# 9_RK3588_USB_Controler.net
KiCad netlist of a schematic drawn in Altium Designer
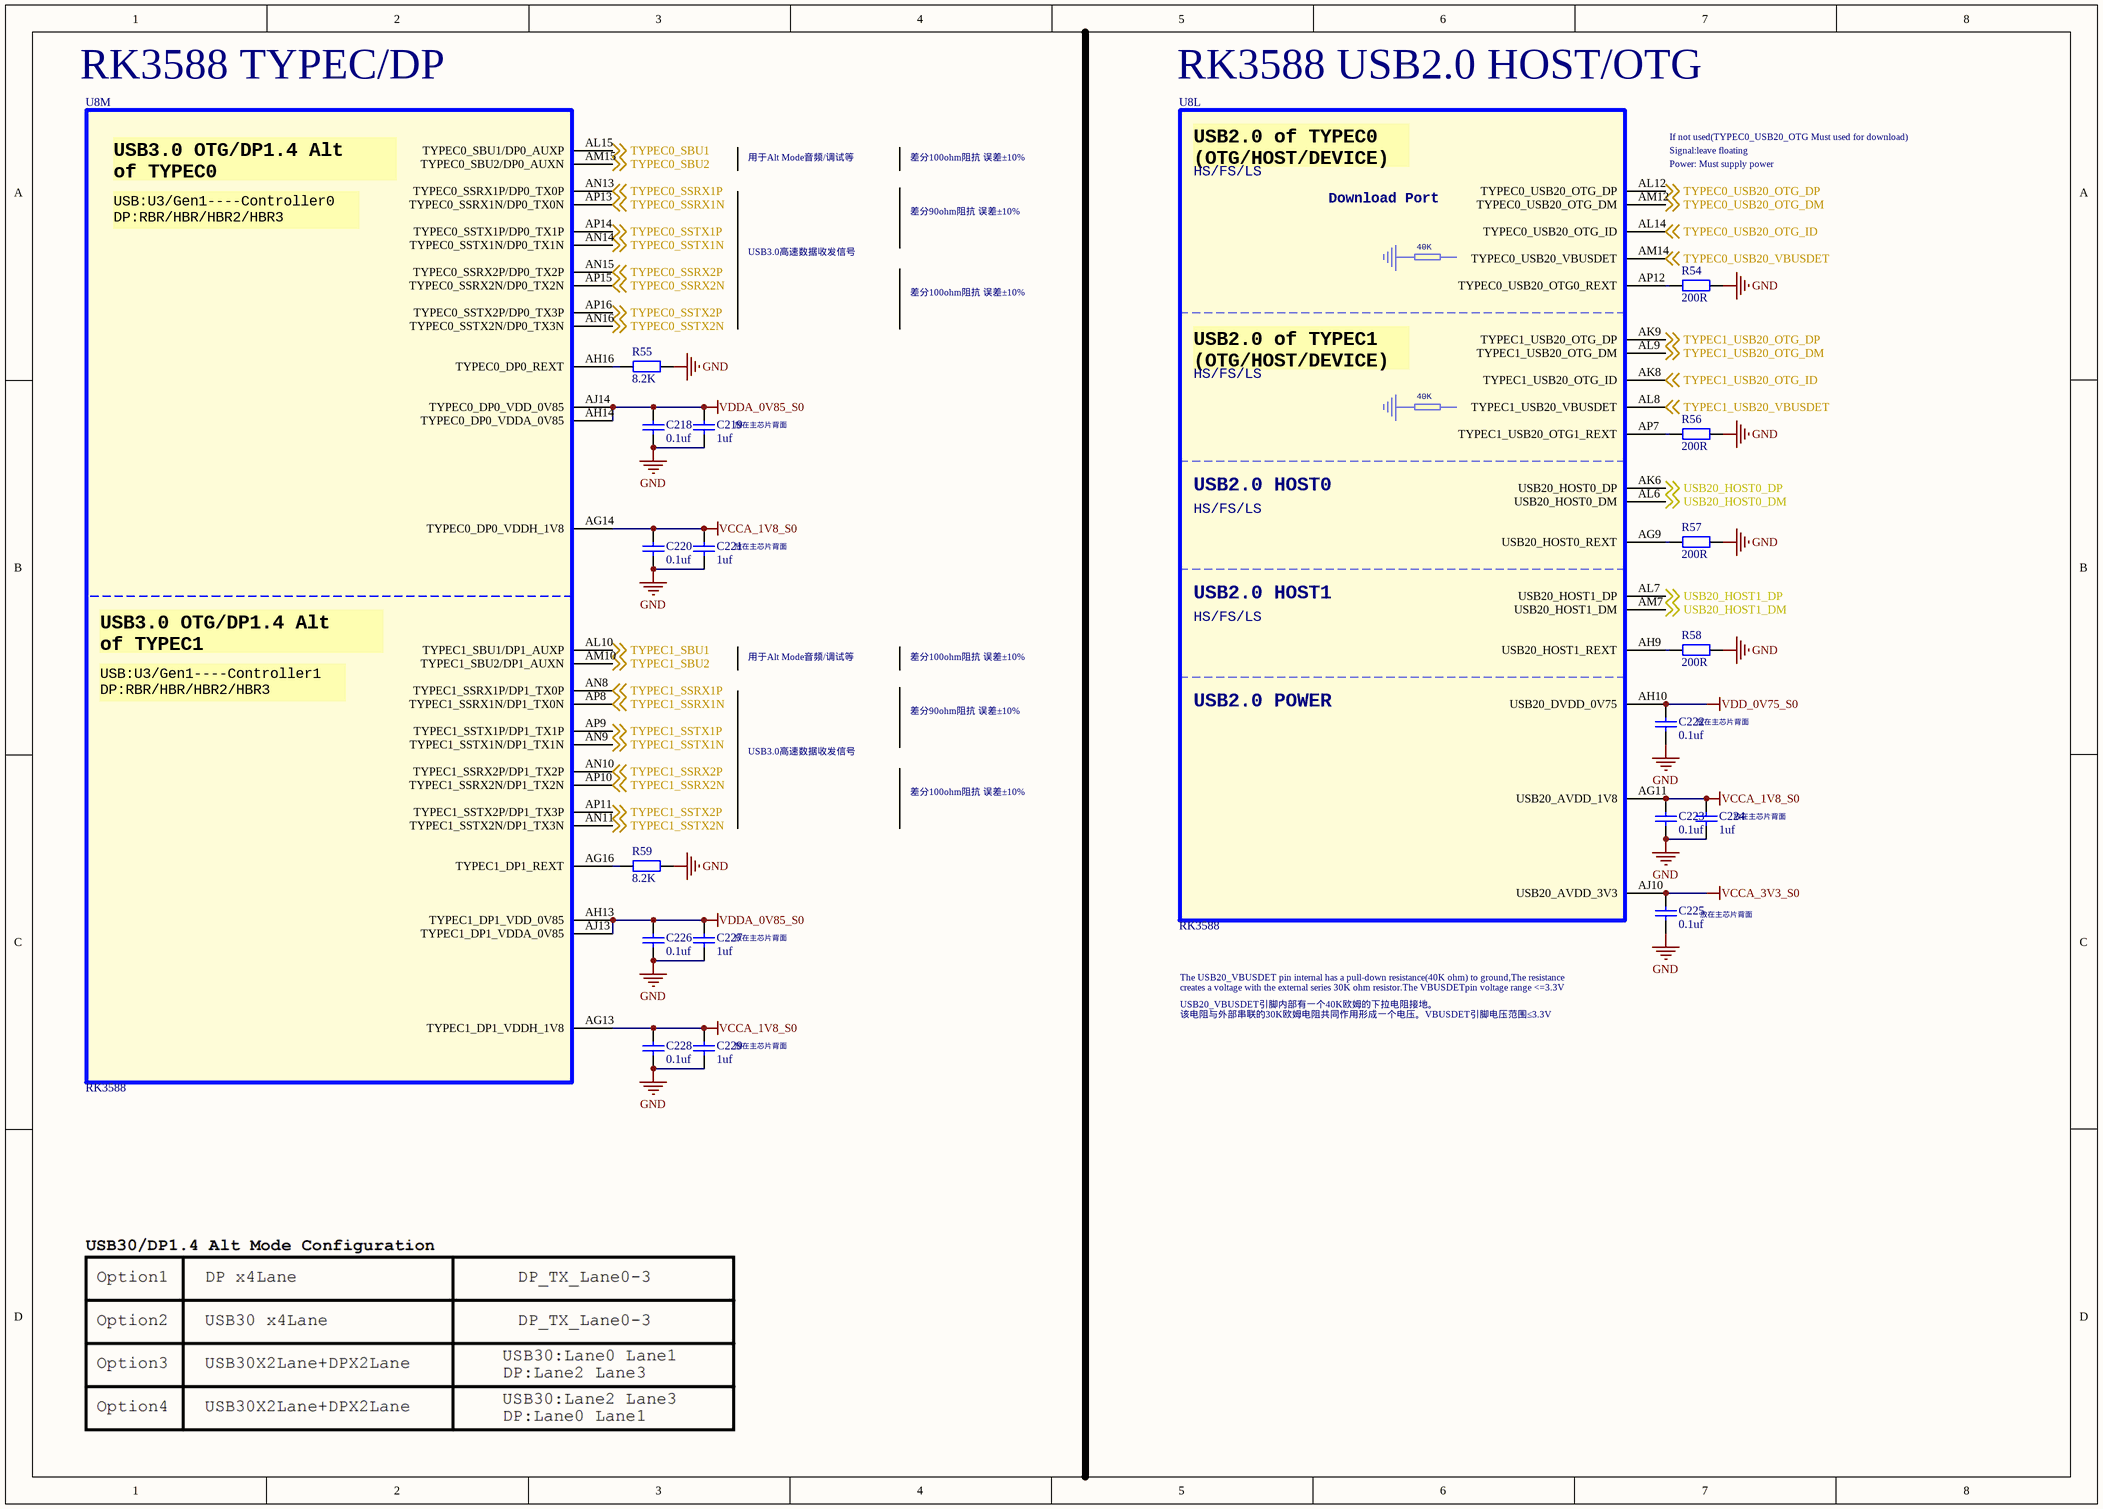
[diagram p0: 9.RK3588_USB_Controler.SchDoc]

(export (version "E")
  (design (tool "Eeschema 10.0.6"))
  (components
    (comp (ref "C218")
      (value "0.1uf")
      (footprint "0.PCB1:C0201_L")
      (description "贴片电容/MLCC电容")
      (libsource (lib "RK3588") (part "C"))
    )
    (comp (ref "C219")
      (value "1uf")
      (footprint "0.PCB1:C0201_L")
      (description "贴片电容/MLCC电容")
      (libsource (lib "RK3588") (part "C"))
    )
    (comp (ref "C220")
      (value "0.1uf")
      (footprint "0.PCB1:C0201_L")
      (description "贴片电容/MLCC电容")
      (libsource (lib "RK3588") (part "C"))
    )
    (comp (ref "C221")
      (value "1uf")
      (footprint "0.PCB1:C0201_L")
      (description "贴片电容/MLCC电容")
      (libsource (lib "RK3588") (part "C"))
    )
    (comp (ref "C222")
      (value "0.1uf")
      (footprint "0.PCB1:C0201_L")
      (description "贴片电容/MLCC电容")
      (libsource (lib "RK3588") (part "C"))
    )
    (comp (ref "C223")
      (value "0.1uf")
      (footprint "0.PCB1:C0201_L")
      (description "贴片电容/MLCC电容")
      (libsource (lib "RK3588") (part "C"))
    )
    (comp (ref "C224")
      (value "1uf")
      (footprint "0.PCB1:C0201_L")
      (description "贴片电容/MLCC电容")
      (libsource (lib "RK3588") (part "C"))
    )
    (comp (ref "C225")
      (value "0.1uf")
      (footprint "0.PCB1:C0201_L")
      (description "贴片电容/MLCC电容")
      (libsource (lib "RK3588") (part "C"))
    )
    (comp (ref "C226")
      (value "0.1uf")
      (footprint "0.PCB1:C0201_L")
      (description "贴片电容/MLCC电容")
      (libsource (lib "RK3588") (part "C"))
    )
    (comp (ref "C227")
      (value "1uf")
      (footprint "0.PCB1:C0201_L")
      (description "贴片电容/MLCC电容")
      (libsource (lib "RK3588") (part "C"))
    )
    (comp (ref "C228")
      (value "0.1uf")
      (footprint "0.PCB1:C0201_L")
      (description "贴片电容/MLCC电容")
      (libsource (lib "RK3588") (part "C"))
    )
    (comp (ref "C229")
      (value "1uf")
      (footprint "0.PCB1:C0201_L")
      (description "贴片电容/MLCC电容")
      (libsource (lib "RK3588") (part "C"))
    )
    (comp (ref "R54")
      (value "200R")
      (footprint "0.PCB1:R0201_L")
      (description "贴片电阻")
      (libsource (lib "RK3588") (part "R"))
    )
    (comp (ref "R55")
      (value "8.2K")
      (footprint "0.PCB1:R0201_L")
      (description "贴片电阻")
      (libsource (lib "RK3588") (part "R"))
    )
    (comp (ref "R56")
      (value "200R")
      (footprint "0.PCB1:R0201_L")
      (description "贴片电阻")
      (libsource (lib "RK3588") (part "R"))
    )
    (comp (ref "R57")
      (value "200R")
      (footprint "0.PCB1:R0201_L")
      (description "贴片电阻")
      (libsource (lib "RK3588") (part "R"))
    )
    (comp (ref "R58")
      (value "200R")
      (footprint "0.PCB1:R0201_L")
      (description "贴片电阻")
      (libsource (lib "RK3588") (part "R"))
    )
    (comp (ref "R59")
      (value "8.2K")
      (footprint "0.PCB1:R0201_L")
      (description "贴片电阻")
      (libsource (lib "RK3588") (part "R"))
    )
    (comp (ref "U8")
      (value "RK3588")
      (footprint "0.PCB1:BGA1088_23R00X23R00X2R00")
      (description "ROCKCHIP SOC")
      (libsource (lib "RK3588") (part "SOC_RK3588"))
    )
  )
  (nets
    (net (code "1") (name "GND") (class "Default")
      (node (ref "C218") (pin "1") (pinfunction "1_1") (pintype "passive"))
      (node (ref "C219") (pin "1") (pinfunction "1_1") (pintype "passive"))
      (node (ref "C220") (pin "1") (pinfunction "1_1") (pintype "passive"))
      (node (ref "C221") (pin "1") (pinfunction "1_1") (pintype "passive"))
      (node (ref "C222") (pin "1") (pinfunction "1_1") (pintype "passive"))
      (node (ref "C223") (pin "1") (pinfunction "1_1") (pintype "passive"))
      (node (ref "C224") (pin "1") (pinfunction "1_1") (pintype "passive"))
      (node (ref "C225") (pin "1") (pinfunction "1_1") (pintype "passive"))
      (node (ref "C226") (pin "1") (pinfunction "1_1") (pintype "passive"))
      (node (ref "C227") (pin "1") (pinfunction "1_1") (pintype "passive"))
      (node (ref "C228") (pin "1") (pinfunction "1_1") (pintype "passive"))
      (node (ref "C229") (pin "1") (pinfunction "1_1") (pintype "passive"))
      (node (ref "R54") (pin "2") (pinfunction "2_2") (pintype "passive"))
      (node (ref "R55") (pin "2") (pinfunction "2_2") (pintype "passive"))
      (node (ref "R56") (pin "2") (pinfunction "2_2") (pintype "passive"))
      (node (ref "R57") (pin "2") (pinfunction "2_2") (pintype "passive"))
      (node (ref "R58") (pin "2") (pinfunction "2_2") (pintype "passive"))
      (node (ref "R59") (pin "2") (pinfunction "2_2") (pintype "passive"))
    )
    (net (code "2") (name "Net-(U8L-TYPEC0_USB20_OTG0_REXT)") (class "Default")
      (node (ref "R54") (pin "1") (pinfunction "1_1") (pintype "passive"))
      (node (ref "U8") (pin "AP12") (pinfunction "TYPEC0_USB20_OTG0_REXT_AP12") (pintype "passive"))
    )
    (net (code "3") (name "Net-(U8L-TYPEC1_USB20_OTG1_REXT)") (class "Default")
      (node (ref "R56") (pin "1") (pinfunction "1_1") (pintype "passive"))
      (node (ref "U8") (pin "AP7") (pinfunction "TYPEC1_USB20_OTG1_REXT_AP7") (pintype "passive"))
    )
    (net (code "4") (name "Net-(U8L-USB20_HOST0_REXT)") (class "Default")
      (node (ref "R57") (pin "1") (pinfunction "1_1") (pintype "passive"))
      (node (ref "U8") (pin "AG9") (pinfunction "USB20_HOST0_REXT_AG9") (pintype "passive"))
    )
    (net (code "5") (name "Net-(U8L-USB20_HOST1_REXT)") (class "Default")
      (node (ref "R58") (pin "1") (pinfunction "1_1") (pintype "passive"))
      (node (ref "U8") (pin "AH9") (pinfunction "USB20_HOST1_REXT_AH9") (pintype "passive"))
    )
    (net (code "6") (name "Net-(U8M-TYPEC0_DP0_REXT)") (class "Default")
      (node (ref "R55") (pin "1") (pinfunction "1_1") (pintype "passive"))
      (node (ref "U8") (pin "AH16") (pinfunction "TYPEC0_DP0_REXT_AH16") (pintype "passive"))
    )
    (net (code "7") (name "Net-(U8M-TYPEC1_DP1_REXT)") (class "Default")
      (node (ref "R59") (pin "1") (pinfunction "1_1") (pintype "passive"))
      (node (ref "U8") (pin "AG16") (pinfunction "TYPEC1_DP1_REXT_AG16") (pintype "passive"))
    )
    (net (code "8") (name "TYPEC0_SBU1") (class "Default")
      (node (ref "U8") (pin "AL15") (pinfunction "TYPEC0_SBU1/DP0_AUXP_AL15") (pintype "passive"))
    )
    (net (code "9") (name "TYPEC0_SBU2") (class "Default")
      (node (ref "U8") (pin "AM15") (pinfunction "TYPEC0_SBU2/DP0_AUXN_AM15") (pintype "passive"))
    )
    (net (code "10") (name "TYPEC0_SSRX1N") (class "Default")
      (node (ref "U8") (pin "AP13") (pinfunction "TYPEC0_SSRX1N/DP0_TX0N_AP13") (pintype "passive"))
    )
    (net (code "11") (name "TYPEC0_SSRX1P") (class "Default")
      (node (ref "U8") (pin "AN13") (pinfunction "TYPEC0_SSRX1P/DP0_TX0P_AN13") (pintype "passive"))
    )
    (net (code "12") (name "TYPEC0_SSRX2N") (class "Default")
      (node (ref "U8") (pin "AP15") (pinfunction "TYPEC0_SSRX2N/DP0_TX2N_AP15") (pintype "passive"))
    )
    (net (code "13") (name "TYPEC0_SSRX2P") (class "Default")
      (node (ref "U8") (pin "AN15") (pinfunction "TYPEC0_SSRX2P/DP0_TX2P_AN15") (pintype "passive"))
    )
    (net (code "14") (name "TYPEC0_SSTX1N") (class "Default")
      (node (ref "U8") (pin "AN14") (pinfunction "TYPEC0_SSTX1N/DP0_TX1N_AN14") (pintype "passive"))
    )
    (net (code "15") (name "TYPEC0_SSTX1P") (class "Default")
      (node (ref "U8") (pin "AP14") (pinfunction "TYPEC0_SSTX1P/DP0_TX1P_AP14") (pintype "passive"))
    )
    (net (code "16") (name "TYPEC0_SSTX2N") (class "Default")
      (node (ref "U8") (pin "AN16") (pinfunction "TYPEC0_SSTX2N/DP0_TX3N_AN16") (pintype "passive"))
    )
    (net (code "17") (name "TYPEC0_SSTX2P") (class "Default")
      (node (ref "U8") (pin "AP16") (pinfunction "TYPEC0_SSTX2P/DP0_TX3P_AP16") (pintype "passive"))
    )
    (net (code "18") (name "TYPEC0_USB20_OTG_DM") (class "Default")
      (node (ref "U8") (pin "AM12") (pinfunction "TYPEC0_USB20_OTG_DM_AM12") (pintype "passive"))
    )
    (net (code "19") (name "TYPEC0_USB20_OTG_DP") (class "Default")
      (node (ref "U8") (pin "AL12") (pinfunction "TYPEC0_USB20_OTG_DP_AL12") (pintype "passive"))
    )
    (net (code "20") (name "TYPEC0_USB20_OTG_ID") (class "Default")
      (node (ref "U8") (pin "AL14") (pinfunction "TYPEC0_USB20_OTG_ID_AL14") (pintype "passive"))
    )
    (net (code "21") (name "TYPEC0_USB20_VBUSDET") (class "Default")
      (node (ref "U8") (pin "AM14") (pinfunction "TYPEC0_USB20_VBUSDET_AM14") (pintype "passive"))
    )
    (net (code "22") (name "TYPEC1_SBU1") (class "Default")
      (node (ref "U8") (pin "AL10") (pinfunction "TYPEC1_SBU1/DP1_AUXP_AL10") (pintype "passive"))
    )
    (net (code "23") (name "TYPEC1_SBU2") (class "Default")
      (node (ref "U8") (pin "AM10") (pinfunction "TYPEC1_SBU2/DP1_AUXN_AM10") (pintype "passive"))
    )
    (net (code "24") (name "TYPEC1_SSRX1N") (class "Default")
      (node (ref "U8") (pin "AP8") (pinfunction "TYPEC1_SSRX1N/DP1_TX0N_AP8") (pintype "passive"))
    )
    (net (code "25") (name "TYPEC1_SSRX1P") (class "Default")
      (node (ref "U8") (pin "AN8") (pinfunction "TYPEC1_SSRX1P/DP1_TX0P_AN8") (pintype "passive"))
    )
    (net (code "26") (name "TYPEC1_SSRX2N") (class "Default")
      (node (ref "U8") (pin "AP10") (pinfunction "TYPEC1_SSRX2N/DP1_TX2N_AP10") (pintype "passive"))
    )
    (net (code "27") (name "TYPEC1_SSRX2P") (class "Default")
      (node (ref "U8") (pin "AN10") (pinfunction "TYPEC1_SSRX2P/DP1_TX2P_AN10") (pintype "passive"))
    )
    (net (code "28") (name "TYPEC1_SSTX1N") (class "Default")
      (node (ref "U8") (pin "AN9") (pinfunction "TYPEC1_SSTX1N/DP1_TX1N_AN9") (pintype "passive"))
    )
    (net (code "29") (name "TYPEC1_SSTX1P") (class "Default")
      (node (ref "U8") (pin "AP9") (pinfunction "TYPEC1_SSTX1P/DP1_TX1P_AP9") (pintype "passive"))
    )
    (net (code "30") (name "TYPEC1_SSTX2N") (class "Default")
      (node (ref "U8") (pin "AN11") (pinfunction "TYPEC1_SSTX2N/DP1_TX3N_AN11") (pintype "passive"))
    )
    (net (code "31") (name "TYPEC1_SSTX2P") (class "Default")
      (node (ref "U8") (pin "AP11") (pinfunction "TYPEC1_SSTX2P/DP1_TX3P_AP11") (pintype "passive"))
    )
    (net (code "32") (name "TYPEC1_USB20_OTG_DM") (class "Default")
      (node (ref "U8") (pin "AL9") (pinfunction "TYPEC1_USB20_OTG_DM_AL9") (pintype "passive"))
    )
    (net (code "33") (name "TYPEC1_USB20_OTG_DP") (class "Default")
      (node (ref "U8") (pin "AK9") (pinfunction "TYPEC1_USB20_OTG_DP_AK9") (pintype "passive"))
    )
    (net (code "34") (name "TYPEC1_USB20_OTG_ID") (class "Default")
      (node (ref "U8") (pin "AK8") (pinfunction "TYPEC1_USB20_OTG_ID_AK8") (pintype "passive"))
    )
    (net (code "35") (name "TYPEC1_USB20_VBUSDET") (class "Default")
      (node (ref "U8") (pin "AL8") (pinfunction "TYPEC1_USB20_VBUSDET_AL8") (pintype "passive"))
    )
    (net (code "36") (name "USB20_HOST0_DM") (class "Default")
      (node (ref "U8") (pin "AL6") (pinfunction "USB20_HOST0_DM_AL6") (pintype "passive"))
    )
    (net (code "37") (name "USB20_HOST0_DP") (class "Default")
      (node (ref "U8") (pin "AK6") (pinfunction "USB20_HOST0_DP_AK6") (pintype "passive"))
    )
    (net (code "38") (name "USB20_HOST1_DM") (class "Default")
      (node (ref "U8") (pin "AM7") (pinfunction "USB20_HOST1_DM_AM7") (pintype "passive"))
    )
    (net (code "39") (name "USB20_HOST1_DP") (class "Default")
      (node (ref "U8") (pin "AL7") (pinfunction "USB20_HOST1_DP_AL7") (pintype "passive"))
    )
    (net (code "40") (name "VCCA_1V8_S0") (class "Default")
      (node (ref "C220") (pin "2") (pinfunction "2_2") (pintype "passive"))
      (node (ref "C221") (pin "2") (pinfunction "2_2") (pintype "passive"))
      (node (ref "C223") (pin "2") (pinfunction "2_2") (pintype "passive"))
      (node (ref "C224") (pin "2") (pinfunction "2_2") (pintype "passive"))
      (node (ref "C228") (pin "2") (pinfunction "2_2") (pintype "passive"))
      (node (ref "C229") (pin "2") (pinfunction "2_2") (pintype "passive"))
      (node (ref "U8") (pin "AG11") (pinfunction "USB20_AVDD_1V8_AG11") (pintype "passive"))
      (node (ref "U8") (pin "AG13") (pinfunction "TYPEC1_DP1_VDDH_1V8_AG13") (pintype "passive"))
      (node (ref "U8") (pin "AG14") (pinfunction "TYPEC0_DP0_VDDH_1V8_AG14") (pintype "passive"))
    )
    (net (code "41") (name "VCCA_3V3_S0") (class "Default")
      (node (ref "C225") (pin "2") (pinfunction "2_2") (pintype "passive"))
      (node (ref "U8") (pin "AJ10") (pinfunction "USB20_AVDD_3V3_AJ10") (pintype "passive"))
    )
    (net (code "42") (name "VDDA_0V85_S0") (class "Default")
      (node (ref "C218") (pin "2") (pinfunction "2_2") (pintype "passive"))
      (node (ref "C219") (pin "2") (pinfunction "2_2") (pintype "passive"))
      (node (ref "C226") (pin "2") (pinfunction "2_2") (pintype "passive"))
      (node (ref "C227") (pin "2") (pinfunction "2_2") (pintype "passive"))
      (node (ref "U8") (pin "AH13") (pinfunction "TYPEC1_DP1_VDD_0V85_AH13") (pintype "passive"))
      (node (ref "U8") (pin "AH14") (pinfunction "TYPEC0_DP0_VDDA_0V85_AH14") (pintype "passive"))
      (node (ref "U8") (pin "AJ13") (pinfunction "TYPEC1_DP1_VDDA_0V85_AJ13") (pintype "passive"))
      (node (ref "U8") (pin "AJ14") (pinfunction "TYPEC0_DP0_VDD_0V85_AJ14") (pintype "passive"))
    )
    (net (code "43") (name "VDD_0V75_S0") (class "Default")
      (node (ref "C222") (pin "2") (pinfunction "2_2") (pintype "passive"))
      (node (ref "U8") (pin "AH10") (pinfunction "USB20_DVDD_0V75_AH10") (pintype "passive"))
    )
  )
)
